# Sensor_AnalogVideo.net
KiCad netlist of a schematic drawn in EAGLE
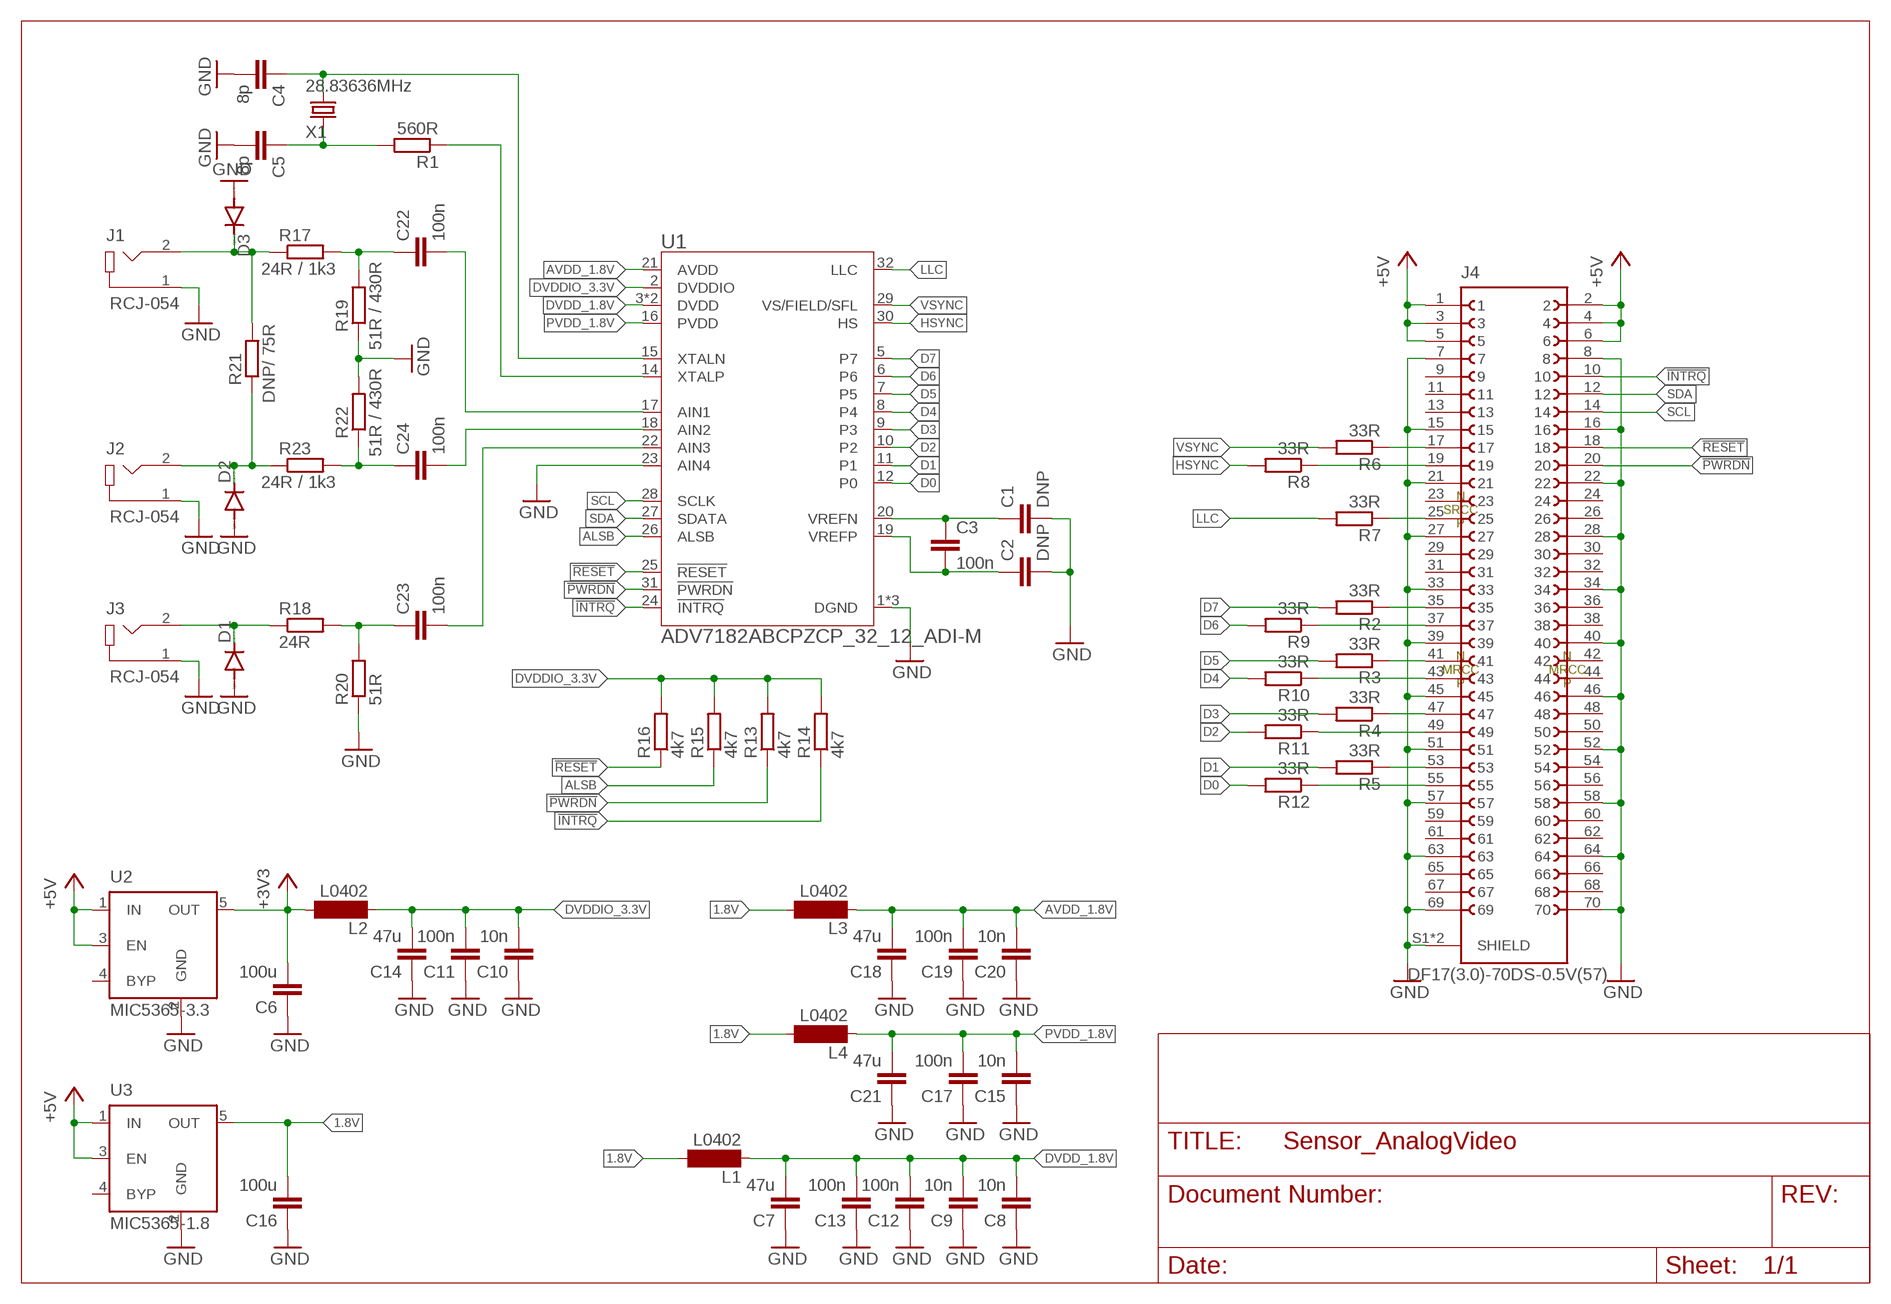
[diagram p0: schematic, sheet 1]

(export (version "E")
  (design (tool "Eeschema 10.0.6"))
  (components
    (comp (ref "C1")
      (value "DNP")
      (footprint "eagle-import:C0402")
      (libsource (lib "eagle-import") (part "rcl_334_C-EUC0402"))
    )
    (comp (ref "C2")
      (value "DNP")
      (footprint "eagle-import:C0402")
      (libsource (lib "eagle-import") (part "rcl_334_C-EUC0402"))
    )
    (comp (ref "C3")
      (value "100n")
      (footprint "eagle-import:C0402")
      (libsource (lib "eagle-import") (part "rcl_334_C-EUC0402"))
    )
    (comp (ref "C4")
      (value "8p")
      (footprint "eagle-import:C0402")
      (libsource (lib "eagle-import") (part "C0402"))
    )
    (comp (ref "C5")
      (value "8p")
      (footprint "eagle-import:C0402")
      (libsource (lib "eagle-import") (part "C0402"))
    )
    (comp (ref "C6")
      (value "100u")
      (footprint "eagle-import:C1206")
      (libsource (lib "eagle-import") (part "rcl_334_C-EUC1206"))
    )
    (comp (ref "C7")
      (value "47u")
      (footprint "eagle-import:C0805")
      (libsource (lib "eagle-import") (part "C-EUC0805"))
    )
    (comp (ref "C8")
      (value "10n")
      (footprint "eagle-import:C0402")
      (libsource (lib "eagle-import") (part "rcl_334_C-EUC0402"))
    )
    (comp (ref "C9")
      (value "10n")
      (footprint "eagle-import:C0402")
      (libsource (lib "eagle-import") (part "rcl_334_C-EUC0402"))
    )
    (comp (ref "C10")
      (value "10n")
      (footprint "eagle-import:C0402")
      (libsource (lib "eagle-import") (part "rcl_334_C-EUC0402"))
    )
    (comp (ref "C11")
      (value "100n")
      (footprint "eagle-import:C0402")
      (libsource (lib "eagle-import") (part "rcl_334_C-EUC0402"))
    )
    (comp (ref "C12")
      (value "100n")
      (footprint "eagle-import:C0402")
      (libsource (lib "eagle-import") (part "rcl_334_C-EUC0402"))
    )
    (comp (ref "C13")
      (value "100n")
      (footprint "eagle-import:C0402")
      (libsource (lib "eagle-import") (part "rcl_334_C-EUC0402"))
    )
    (comp (ref "C14")
      (value "47u")
      (footprint "eagle-import:C0805")
      (libsource (lib "eagle-import") (part "C-EUC0805"))
    )
    (comp (ref "C15")
      (value "10n")
      (footprint "eagle-import:C0402")
      (libsource (lib "eagle-import") (part "rcl_334_C-EUC0402"))
    )
    (comp (ref "C16")
      (value "100u")
      (footprint "eagle-import:C1206")
      (libsource (lib "eagle-import") (part "rcl_334_C-EUC1206"))
    )
    (comp (ref "C17")
      (value "100n")
      (footprint "eagle-import:C0402")
      (libsource (lib "eagle-import") (part "rcl_334_C-EUC0402"))
    )
    (comp (ref "C18")
      (value "47u")
      (footprint "eagle-import:C0805")
      (libsource (lib "eagle-import") (part "C-EUC0805"))
    )
    (comp (ref "C19")
      (value "100n")
      (footprint "eagle-import:C0402")
      (libsource (lib "eagle-import") (part "rcl_334_C-EUC0402"))
    )
    (comp (ref "C20")
      (value "10n")
      (footprint "eagle-import:C0402")
      (libsource (lib "eagle-import") (part "rcl_334_C-EUC0402"))
    )
    (comp (ref "C21")
      (value "47u")
      (footprint "eagle-import:C0805")
      (libsource (lib "eagle-import") (part "C-EUC0805"))
    )
    (comp (ref "C22")
      (value "100n")
      (footprint "eagle-import:C0402")
      (libsource (lib "eagle-import") (part "rcl_334_C-EUC0402"))
    )
    (comp (ref "C23")
      (value "100n")
      (footprint "eagle-import:C0402")
      (libsource (lib "eagle-import") (part "rcl_334_C-EUC0402"))
    )
    (comp (ref "C24")
      (value "100n")
      (footprint "eagle-import:C0402")
      (libsource (lib "eagle-import") (part "rcl_334_C-EUC0402"))
    )
    (comp (ref "D1")
      (value "DIODE-SOD323-W")
      (footprint "eagle-import:SOD323-W")
      (libsource (lib "eagle-import") (part "DIODE-SOD323-W"))
    )
    (comp (ref "D2")
      (value "DIODE-SOD323-W")
      (footprint "eagle-import:SOD323-W")
      (libsource (lib "eagle-import") (part "DIODE-SOD323-W"))
    )
    (comp (ref "D3")
      (value "DIODE-SOD323-W")
      (footprint "eagle-import:SOD323-W")
      (libsource (lib "eagle-import") (part "DIODE-SOD323-W"))
    )
    (comp (ref "J1")
      (value "RCJ-054")
      (footprint "eagle-import:CUI_RCJ-054")
      (fields (field (name "MF") "CUI Devices"))
      (libsource (lib "eagle-import") (part "RCJ-054"))
    )
    (comp (ref "J2")
      (value "RCJ-054")
      (footprint "eagle-import:CUI_RCJ-054")
      (fields (field (name "MF") "CUI Devices"))
      (libsource (lib "eagle-import") (part "RCJ-054"))
    )
    (comp (ref "J3")
      (value "RCJ-054")
      (footprint "eagle-import:CUI_RCJ-054")
      (fields (field (name "MF") "CUI Devices"))
      (libsource (lib "eagle-import") (part "RCJ-054"))
    )
    (comp (ref "J4")
      (value "DF17(3.0)-70DS-0.5V(57)")
      (footprint "eagle-import:DF17(3.0)-70DS-0.5V(57)")
      (libsource (lib "eagle-import") (part "DF17(3.0)-70DS-0.5V(57)"))
    )
    (comp (ref "L1")
      (value "L0402")
      (footprint "eagle-import:C0402")
      (libsource (lib "eagle-import") (part "L0402"))
    )
    (comp (ref "L2")
      (value "L0402")
      (footprint "eagle-import:C0402")
      (libsource (lib "eagle-import") (part "L0402"))
    )
    (comp (ref "L3")
      (value "L0402")
      (footprint "eagle-import:C0402")
      (libsource (lib "eagle-import") (part "L0402"))
    )
    (comp (ref "L4")
      (value "L0402")
      (footprint "eagle-import:C0402")
      (libsource (lib "eagle-import") (part "L0402"))
    )
    (comp (ref "R1")
      (value "560R")
      (footprint "eagle-import:R0402")
      (libsource (lib "eagle-import") (part "R-EU_R0402"))
    )
    (comp (ref "R2")
      (value "33R")
      (footprint "eagle-import:R0402")
      (libsource (lib "eagle-import") (part "R-EU_R0402"))
    )
    (comp (ref "R3")
      (value "33R")
      (footprint "eagle-import:R0402")
      (libsource (lib "eagle-import") (part "R-EU_R0402"))
    )
    (comp (ref "R4")
      (value "33R")
      (footprint "eagle-import:R0402")
      (libsource (lib "eagle-import") (part "R-EU_R0402"))
    )
    (comp (ref "R5")
      (value "33R")
      (footprint "eagle-import:R0402")
      (libsource (lib "eagle-import") (part "R-EU_R0402"))
    )
    (comp (ref "R6")
      (value "33R")
      (footprint "eagle-import:R0402")
      (libsource (lib "eagle-import") (part "R-EU_R0402"))
    )
    (comp (ref "R7")
      (value "33R")
      (footprint "eagle-import:R0402")
      (libsource (lib "eagle-import") (part "R-EU_R0402"))
    )
    (comp (ref "R8")
      (value "33R")
      (footprint "eagle-import:R0402")
      (libsource (lib "eagle-import") (part "R-EU_R0402"))
    )
    (comp (ref "R9")
      (value "33R")
      (footprint "eagle-import:R0402")
      (libsource (lib "eagle-import") (part "R-EU_R0402"))
    )
    (comp (ref "R10")
      (value "33R")
      (footprint "eagle-import:R0402")
      (libsource (lib "eagle-import") (part "R-EU_R0402"))
    )
    (comp (ref "R11")
      (value "33R")
      (footprint "eagle-import:R0402")
      (libsource (lib "eagle-import") (part "R-EU_R0402"))
    )
    (comp (ref "R12")
      (value "33R")
      (footprint "eagle-import:R0402")
      (libsource (lib "eagle-import") (part "R-EU_R0402"))
    )
    (comp (ref "R13")
      (value "4k7")
      (footprint "eagle-import:R0402")
      (libsource (lib "eagle-import") (part "R-EU_R0402"))
    )
    (comp (ref "R14")
      (value "4k7")
      (footprint "eagle-import:R0402")
      (libsource (lib "eagle-import") (part "R-EU_R0402"))
    )
    (comp (ref "R15")
      (value "4k7")
      (footprint "eagle-import:R0402")
      (libsource (lib "eagle-import") (part "R-EU_R0402"))
    )
    (comp (ref "R16")
      (value "4k7")
      (footprint "eagle-import:R0402")
      (libsource (lib "eagle-import") (part "R-EU_R0402"))
    )
    (comp (ref "R17")
      (value "24R / 1k3")
      (footprint "eagle-import:R0603")
      (libsource (lib "eagle-import") (part "R-EU_R0603"))
    )
    (comp (ref "R18")
      (value "24R")
      (footprint "eagle-import:R0603")
      (libsource (lib "eagle-import") (part "R-EU_R0603"))
    )
    (comp (ref "R19")
      (value "51R / 430R")
      (footprint "eagle-import:R0603")
      (libsource (lib "eagle-import") (part "R-EU_R0603"))
    )
    (comp (ref "R20")
      (value "51R")
      (footprint "eagle-import:R0603")
      (libsource (lib "eagle-import") (part "R-EU_R0603"))
    )
    (comp (ref "R21")
      (value "DNP/ 75R")
      (footprint "eagle-import:R0603")
      (libsource (lib "eagle-import") (part "R-EU_R0603"))
    )
    (comp (ref "R22")
      (value "51R / 430R")
      (footprint "eagle-import:R0603")
      (libsource (lib "eagle-import") (part "R-EU_R0603"))
    )
    (comp (ref "R23")
      (value "24R / 1k3")
      (footprint "eagle-import:R0603")
      (libsource (lib "eagle-import") (part "R-EU_R0603"))
    )
    (comp (ref "U1")
      (value "ADV7182ABCPZCP_32_12_ADI-M")
      (footprint "eagle-import:CP_32_12_ADI-M")
      (fields (field (name "MPN") "ADV7182ABCPZ"))
      (libsource (lib "eagle-import") (part "ADV7182ABCPZCP_32_12_ADI-M"))
    )
    (comp (ref "U2")
      (value "MIC5365-3.3")
      (footprint "eagle-import:SOT23-5")
      (libsource (lib "eagle-import") (part "MIC5219XX"))
    )
    (comp (ref "U3")
      (value "MIC5365-1.8")
      (footprint "eagle-import:SOT23-5")
      (libsource (lib "eagle-import") (part "MIC5219XX"))
    )
    (comp (ref "X1")
      (value "28.83636MHz")
      (footprint "eagle-import:2520")
      (libsource (lib "eagle-import") (part "CRYSTAL-2520"))
    )
  )
  (nets
    (net (code "1") (name "+3V3") (class "Default")
      (node (ref "C6") (pin "1") (pinfunction "1_1") (pintype "passive"))
      (node (ref "L2") (pin "2") (pinfunction "2_2") (pintype "passive"))
      (node (ref "U2") (pin "5") (pinfunction "OUT_5") (pintype "output"))
    )
    (net (code "2") (name "+5V") (class "Default")
      (node (ref "J4") (pin "1") (pinfunction "1_1") (pintype "passive"))
      (node (ref "J4") (pin "2") (pinfunction "2_2") (pintype "passive"))
      (node (ref "J4") (pin "3") (pinfunction "3_3") (pintype "passive"))
      (node (ref "J4") (pin "4") (pinfunction "4_4") (pintype "passive"))
      (node (ref "J4") (pin "5") (pinfunction "5_5") (pintype "passive"))
      (node (ref "J4") (pin "6") (pinfunction "6_6") (pintype "passive"))
      (node (ref "U2") (pin "1") (pinfunction "IN_1") (pintype "input"))
      (node (ref "U2") (pin "3") (pinfunction "EN_3") (pintype "input"))
      (node (ref "U3") (pin "1") (pinfunction "IN_1") (pintype "input"))
      (node (ref "U3") (pin "3") (pinfunction "EN_3") (pintype "input"))
    )
    (net (code "3") (name "/~{INTRQ}") (class "Default")
      (node (ref "J4") (pin "10") (pinfunction "10_10") (pintype "passive"))
      (node (ref "R14") (pin "1") (pinfunction "1_1") (pintype "passive"))
      (node (ref "U1") (pin "24") (pinfunction "~{INTRQ}_24") (pintype "passive"))
    )
    (net (code "4") (name "/~{PWRDN}") (class "Default")
      (node (ref "J4") (pin "20") (pinfunction "20_20") (pintype "passive"))
      (node (ref "R13") (pin "1") (pinfunction "1_1") (pintype "passive"))
      (node (ref "U1") (pin "31") (pinfunction "~{PWRDN}_31") (pintype "passive"))
    )
    (net (code "5") (name "/~{RESET}") (class "Default")
      (node (ref "J4") (pin "18") (pinfunction "18_18") (pintype "passive"))
      (node (ref "R16") (pin "1") (pinfunction "1_1") (pintype "passive"))
      (node (ref "U1") (pin "25") (pinfunction "~{RESET}_25") (pintype "passive"))
    )
    (net (code "6") (name "1.8V") (class "Default")
      (node (ref "C16") (pin "1") (pinfunction "1_1") (pintype "passive"))
      (node (ref "L1") (pin "2") (pinfunction "2_2") (pintype "passive"))
      (node (ref "L3") (pin "2") (pinfunction "2_2") (pintype "passive"))
      (node (ref "L4") (pin "2") (pinfunction "2_2") (pintype "passive"))
      (node (ref "U3") (pin "5") (pinfunction "OUT_5") (pintype "output"))
    )
    (net (code "7") (name "ALSB") (class "Default")
      (node (ref "R15") (pin "1") (pinfunction "1_1") (pintype "passive"))
      (node (ref "U1") (pin "26") (pinfunction "ALSB_26") (pintype "passive"))
    )
    (net (code "8") (name "AVDD_1.8V") (class "Default")
      (node (ref "C18") (pin "2") (pinfunction "2_2") (pintype "passive"))
      (node (ref "C19") (pin "2") (pinfunction "2_2") (pintype "passive"))
      (node (ref "C20") (pin "2") (pinfunction "2_2") (pintype "passive"))
      (node (ref "L3") (pin "1") (pinfunction "1_1") (pintype "passive"))
      (node (ref "U1") (pin "21") (pinfunction "AVDD_21") (pintype "passive"))
    )
    (net (code "9") (name "D0") (class "Default")
      (node (ref "R12") (pin "2") (pinfunction "2_2") (pintype "passive"))
      (node (ref "U1") (pin "12") (pinfunction "P0_12") (pintype "passive"))
    )
    (net (code "10") (name "D1") (class "Default")
      (node (ref "R5") (pin "2") (pinfunction "2_2") (pintype "passive"))
      (node (ref "U1") (pin "11") (pinfunction "P1_11") (pintype "passive"))
    )
    (net (code "11") (name "D2") (class "Default")
      (node (ref "R11") (pin "2") (pinfunction "2_2") (pintype "passive"))
      (node (ref "U1") (pin "10") (pinfunction "P2_10") (pintype "passive"))
    )
    (net (code "12") (name "D3") (class "Default")
      (node (ref "R4") (pin "2") (pinfunction "2_2") (pintype "passive"))
      (node (ref "U1") (pin "9") (pinfunction "P3_9") (pintype "passive"))
    )
    (net (code "13") (name "D4") (class "Default")
      (node (ref "R10") (pin "2") (pinfunction "2_2") (pintype "passive"))
      (node (ref "U1") (pin "8") (pinfunction "P4_8") (pintype "passive"))
    )
    (net (code "14") (name "D5") (class "Default")
      (node (ref "R3") (pin "2") (pinfunction "2_2") (pintype "passive"))
      (node (ref "U1") (pin "7") (pinfunction "P5_7") (pintype "passive"))
    )
    (net (code "15") (name "D6") (class "Default")
      (node (ref "R9") (pin "2") (pinfunction "2_2") (pintype "passive"))
      (node (ref "U1") (pin "6") (pinfunction "P6_6") (pintype "passive"))
    )
    (net (code "16") (name "D7") (class "Default")
      (node (ref "R2") (pin "2") (pinfunction "2_2") (pintype "passive"))
      (node (ref "U1") (pin "5") (pinfunction "P7_5") (pintype "passive"))
    )
    (net (code "17") (name "DVDDIO_3.3V") (class "Default")
      (node (ref "C10") (pin "2") (pinfunction "2_2") (pintype "passive"))
      (node (ref "C11") (pin "2") (pinfunction "2_2") (pintype "passive"))
      (node (ref "C14") (pin "2") (pinfunction "2_2") (pintype "passive"))
      (node (ref "L2") (pin "1") (pinfunction "1_1") (pintype "passive"))
      (node (ref "R13") (pin "2") (pinfunction "2_2") (pintype "passive"))
      (node (ref "R14") (pin "2") (pinfunction "2_2") (pintype "passive"))
      (node (ref "R15") (pin "2") (pinfunction "2_2") (pintype "passive"))
      (node (ref "R16") (pin "2") (pinfunction "2_2") (pintype "passive"))
      (node (ref "U1") (pin "2") (pinfunction "DVDDIO_2") (pintype "passive"))
    )
    (net (code "18") (name "DVDD_1.8V") (class "Default")
      (node (ref "C12") (pin "2") (pinfunction "2_2") (pintype "passive"))
      (node (ref "C13") (pin "2") (pinfunction "2_2") (pintype "passive"))
      (node (ref "C7") (pin "2") (pinfunction "2_2") (pintype "passive"))
      (node (ref "C8") (pin "2") (pinfunction "2_2") (pintype "passive"))
      (node (ref "C9") (pin "2") (pinfunction "2_2") (pintype "passive"))
      (node (ref "L1") (pin "1") (pinfunction "1_1") (pintype "passive"))
      (node (ref "U1") (pin "13") (pinfunction "DVDD_13") (pintype "passive"))
      (node (ref "U1") (pin "3") (pinfunction "DVDD_3") (pintype "passive"))
    )
    (net (code "19") (name "GND") (class "Default")
      (node (ref "C1") (pin "2") (pinfunction "2_2") (pintype "passive"))
      (node (ref "C10") (pin "1") (pinfunction "1_1") (pintype "passive"))
      (node (ref "C11") (pin "1") (pinfunction "1_1") (pintype "passive"))
      (node (ref "C12") (pin "1") (pinfunction "1_1") (pintype "passive"))
      (node (ref "C13") (pin "1") (pinfunction "1_1") (pintype "passive"))
      (node (ref "C14") (pin "1") (pinfunction "1_1") (pintype "passive"))
      (node (ref "C15") (pin "1") (pinfunction "1_1") (pintype "passive"))
      (node (ref "C16") (pin "2") (pinfunction "2_2") (pintype "passive"))
      (node (ref "C17") (pin "1") (pinfunction "1_1") (pintype "passive"))
      (node (ref "C18") (pin "1") (pinfunction "1_1") (pintype "passive"))
      (node (ref "C19") (pin "1") (pinfunction "1_1") (pintype "passive"))
      (node (ref "C2") (pin "2") (pinfunction "2_2") (pintype "passive"))
      (node (ref "C20") (pin "1") (pinfunction "1_1") (pintype "passive"))
      (node (ref "C21") (pin "1") (pinfunction "1_1") (pintype "passive"))
      (node (ref "C4") (pin "2") (pinfunction "2_2") (pintype "passive"))
      (node (ref "C5") (pin "2") (pinfunction "2_2") (pintype "passive"))
      (node (ref "C6") (pin "2") (pinfunction "2_2") (pintype "passive"))
      (node (ref "C7") (pin "1") (pinfunction "1_1") (pintype "passive"))
      (node (ref "C8") (pin "1") (pinfunction "1_1") (pintype "passive"))
      (node (ref "C9") (pin "1") (pinfunction "1_1") (pintype "passive"))
      (node (ref "D1") (pin "A") (pinfunction "A_A") (pintype "passive"))
      (node (ref "D2") (pin "A") (pinfunction "A_A") (pintype "passive"))
      (node (ref "D3") (pin "A") (pinfunction "A_A") (pintype "passive"))
      (node (ref "J1") (pin "1") (pinfunction "1_1") (pintype "passive"))
      (node (ref "J2") (pin "1") (pinfunction "1_1") (pintype "passive"))
      (node (ref "J3") (pin "1") (pinfunction "1_1") (pintype "passive"))
      (node (ref "J4") (pin "15") (pinfunction "15_15") (pintype "passive"))
      (node (ref "J4") (pin "16") (pinfunction "16_16") (pintype "passive"))
      (node (ref "J4") (pin "21") (pinfunction "21_21") (pintype "passive"))
      (node (ref "J4") (pin "22") (pinfunction "22_22") (pintype "passive"))
      (node (ref "J4") (pin "27") (pinfunction "27_27") (pintype "passive"))
      (node (ref "J4") (pin "28") (pinfunction "28_28") (pintype "passive"))
      (node (ref "J4") (pin "33") (pinfunction "33_33") (pintype "passive"))
      (node (ref "J4") (pin "34") (pinfunction "34_34") (pintype "passive"))
      (node (ref "J4") (pin "39") (pinfunction "39_39") (pintype "passive"))
      (node (ref "J4") (pin "40") (pinfunction "40_40") (pintype "passive"))
      (node (ref "J4") (pin "45") (pinfunction "45_45") (pintype "passive"))
      (node (ref "J4") (pin "46") (pinfunction "46_46") (pintype "passive"))
      (node (ref "J4") (pin "51") (pinfunction "51_51") (pintype "passive"))
      (node (ref "J4") (pin "52") (pinfunction "52_52") (pintype "passive"))
      (node (ref "J4") (pin "57") (pinfunction "57_57") (pintype "passive"))
      (node (ref "J4") (pin "58") (pinfunction "58_58") (pintype "passive"))
      (node (ref "J4") (pin "63") (pinfunction "63_63") (pintype "passive"))
      (node (ref "J4") (pin "64") (pinfunction "64_64") (pintype "passive"))
      (node (ref "J4") (pin "69") (pinfunction "69_69") (pintype "passive"))
      (node (ref "J4") (pin "7") (pinfunction "7_7") (pintype "passive"))
      (node (ref "J4") (pin "70") (pinfunction "70_70") (pintype "passive"))
      (node (ref "J4") (pin "8") (pinfunction "8_8") (pintype "passive"))
      (node (ref "J4") (pin "S1") (pinfunction "SHIELD_S1") (pintype "passive"))
      (node (ref "J4") (pin "S2") (pinfunction "SHIELD_S2") (pintype "passive"))
      (node (ref "R19") (pin "1") (pinfunction "1_1") (pintype "passive"))
      (node (ref "R20") (pin "1") (pinfunction "1_1") (pintype "passive"))
      (node (ref "R22") (pin "2") (pinfunction "2_2") (pintype "passive"))
      (node (ref "U1") (pin "1") (pinfunction "DGND_1") (pintype "passive"))
      (node (ref "U1") (pin "23") (pinfunction "AIN4_23") (pintype "passive"))
      (node (ref "U1") (pin "33") (pinfunction "DGND_33") (pintype "passive"))
      (node (ref "U1") (pin "4") (pinfunction "DGND_4") (pintype "passive"))
      (node (ref "U2") (pin "2") (pinfunction "GND_2") (pintype "power_in"))
      (node (ref "U3") (pin "2") (pinfunction "GND_2") (pintype "power_in"))
    )
    (net (code "20") (name "HSYNC") (class "Default")
      (node (ref "R8") (pin "2") (pinfunction "2_2") (pintype "passive"))
      (node (ref "U1") (pin "30") (pinfunction "HS_30") (pintype "passive"))
    )
    (net (code "21") (name "LLC") (class "Default")
      (node (ref "R7") (pin "2") (pinfunction "2_2") (pintype "passive"))
      (node (ref "U1") (pin "32") (pinfunction "LLC_32") (pintype "passive"))
    )
    (net (code "22") (name "Net-(C22-Pad1)") (class "Default")
      (node (ref "C22") (pin "1") (pinfunction "1_1") (pintype "passive"))
      (node (ref "R17") (pin "2") (pinfunction "2_2") (pintype "passive"))
      (node (ref "R19") (pin "2") (pinfunction "2_2") (pintype "passive"))
    )
    (net (code "23") (name "Net-(C23-Pad1)") (class "Default")
      (node (ref "C23") (pin "1") (pinfunction "1_1") (pintype "passive"))
      (node (ref "R18") (pin "2") (pinfunction "2_2") (pintype "passive"))
      (node (ref "R20") (pin "2") (pinfunction "2_2") (pintype "passive"))
    )
    (net (code "24") (name "Net-(C24-Pad1)") (class "Default")
      (node (ref "C24") (pin "1") (pinfunction "1_1") (pintype "passive"))
      (node (ref "R22") (pin "1") (pinfunction "1_1") (pintype "passive"))
      (node (ref "R23") (pin "2") (pinfunction "2_2") (pintype "passive"))
    )
    (net (code "25") (name "Net-(D1-PadC)") (class "Default")
      (node (ref "D1") (pin "C") (pinfunction "C_C") (pintype "passive"))
      (node (ref "J3") (pin "2") (pinfunction "2_2") (pintype "passive"))
      (node (ref "R18") (pin "1") (pinfunction "1_1") (pintype "passive"))
    )
    (net (code "26") (name "Net-(D2-PadC)") (class "Default")
      (node (ref "D2") (pin "C") (pinfunction "C_C") (pintype "passive"))
      (node (ref "J2") (pin "2") (pinfunction "2_2") (pintype "passive"))
      (node (ref "R21") (pin "1") (pinfunction "1_1") (pintype "passive"))
      (node (ref "R23") (pin "1") (pinfunction "1_1") (pintype "passive"))
    )
    (net (code "27") (name "Net-(D3-PadC)") (class "Default")
      (node (ref "D3") (pin "C") (pinfunction "C_C") (pintype "passive"))
      (node (ref "J1") (pin "2") (pinfunction "2_2") (pintype "passive"))
      (node (ref "R17") (pin "1") (pinfunction "1_1") (pintype "passive"))
      (node (ref "R21") (pin "2") (pinfunction "2_2") (pintype "passive"))
    )
    (net (code "28") (name "Net-(J4-Pad17)") (class "Default")
      (node (ref "J4") (pin "17") (pinfunction "17_17") (pintype "passive"))
      (node (ref "R6") (pin "1") (pinfunction "1_1") (pintype "passive"))
    )
    (net (code "29") (name "Net-(J4-Pad19)") (class "Default")
      (node (ref "J4") (pin "19") (pinfunction "19_19") (pintype "passive"))
      (node (ref "R8") (pin "1") (pinfunction "1_1") (pintype "passive"))
    )
    (net (code "30") (name "Net-(J4-Pad25)") (class "Default")
      (node (ref "J4") (pin "25") (pinfunction "25_25") (pintype "passive"))
      (node (ref "R7") (pin "1") (pinfunction "1_1") (pintype "passive"))
    )
    (net (code "31") (name "Net-(J4-Pad35)") (class "Default")
      (node (ref "J4") (pin "35") (pinfunction "35_35") (pintype "passive"))
      (node (ref "R2") (pin "1") (pinfunction "1_1") (pintype "passive"))
    )
    (net (code "32") (name "Net-(J4-Pad37)") (class "Default")
      (node (ref "J4") (pin "37") (pinfunction "37_37") (pintype "passive"))
      (node (ref "R9") (pin "1") (pinfunction "1_1") (pintype "passive"))
    )
    (net (code "33") (name "Net-(J4-Pad41)") (class "Default")
      (node (ref "J4") (pin "41") (pinfunction "41_41") (pintype "passive"))
      (node (ref "R3") (pin "1") (pinfunction "1_1") (pintype "passive"))
    )
    (net (code "34") (name "Net-(J4-Pad43)") (class "Default")
      (node (ref "J4") (pin "43") (pinfunction "43_43") (pintype "passive"))
      (node (ref "R10") (pin "1") (pinfunction "1_1") (pintype "passive"))
    )
    (net (code "35") (name "Net-(J4-Pad47)") (class "Default")
      (node (ref "J4") (pin "47") (pinfunction "47_47") (pintype "passive"))
      (node (ref "R4") (pin "1") (pinfunction "1_1") (pintype "passive"))
    )
    (net (code "36") (name "Net-(J4-Pad49)") (class "Default")
      (node (ref "J4") (pin "49") (pinfunction "49_49") (pintype "passive"))
      (node (ref "R11") (pin "1") (pinfunction "1_1") (pintype "passive"))
    )
    (net (code "37") (name "Net-(J4-Pad53)") (class "Default")
      (node (ref "J4") (pin "53") (pinfunction "53_53") (pintype "passive"))
      (node (ref "R5") (pin "1") (pinfunction "1_1") (pintype "passive"))
    )
    (net (code "38") (name "Net-(J4-Pad55)") (class "Default")
      (node (ref "J4") (pin "55") (pinfunction "55_55") (pintype "passive"))
      (node (ref "R12") (pin "1") (pinfunction "1_1") (pintype "passive"))
    )
    (net (code "39") (name "Net-(U1-AIN1)") (class "Default")
      (node (ref "C22") (pin "2") (pinfunction "2_2") (pintype "passive"))
      (node (ref "U1") (pin "17") (pinfunction "AIN1_17") (pintype "passive"))
    )
    (net (code "40") (name "Net-(U1-AIN2)") (class "Default")
      (node (ref "C24") (pin "2") (pinfunction "2_2") (pintype "passive"))
      (node (ref "U1") (pin "18") (pinfunction "AIN2_18") (pintype "passive"))
    )
    (net (code "41") (name "Net-(U1-AIN3)") (class "Default")
      (node (ref "C23") (pin "2") (pinfunction "2_2") (pintype "passive"))
      (node (ref "U1") (pin "22") (pinfunction "AIN3_22") (pintype "passive"))
    )
    (net (code "42") (name "Net-(U1-VREFN)") (class "Default")
      (node (ref "C1") (pin "1") (pinfunction "1_1") (pintype "passive"))
      (node (ref "C3") (pin "1") (pinfunction "1_1") (pintype "passive"))
      (node (ref "U1") (pin "20") (pinfunction "VREFN_20") (pintype "passive"))
    )
    (net (code "43") (name "Net-(U1-VREFP)") (class "Default")
      (node (ref "C2") (pin "1") (pinfunction "1_1") (pintype "passive"))
      (node (ref "C3") (pin "2") (pinfunction "2_2") (pintype "passive"))
      (node (ref "U1") (pin "19") (pinfunction "VREFP_19") (pintype "passive"))
    )
    (net (code "44") (name "Net-(U1-XTALN)") (class "Default")
      (node (ref "C4") (pin "1") (pinfunction "1_1") (pintype "passive"))
      (node (ref "U1") (pin "15") (pinfunction "XTALN_15") (pintype "passive"))
      (node (ref "X1") (pin "1") (pinfunction "1_1") (pintype "passive"))
    )
    (net (code "45") (name "Net-(U1-XTALP)") (class "Default")
      (node (ref "R1") (pin "1") (pinfunction "1_1") (pintype "passive"))
      (node (ref "U1") (pin "14") (pinfunction "XTALP_14") (pintype "passive"))
    )
    (net (code "46") (name "Net-(X1-2)") (class "Default")
      (node (ref "C5") (pin "1") (pinfunction "1_1") (pintype "passive"))
      (node (ref "R1") (pin "2") (pinfunction "2_2") (pintype "passive"))
      (node (ref "X1") (pin "3") (pinfunction "2_3") (pintype "passive"))
    )
    (net (code "47") (name "PVDD_1.8V") (class "Default")
      (node (ref "C15") (pin "2") (pinfunction "2_2") (pintype "passive"))
      (node (ref "C17") (pin "2") (pinfunction "2_2") (pintype "passive"))
      (node (ref "C21") (pin "2") (pinfunction "2_2") (pintype "passive"))
      (node (ref "L4") (pin "1") (pinfunction "1_1") (pintype "passive"))
      (node (ref "U1") (pin "16") (pinfunction "PVDD_16") (pintype "passive"))
    )
    (net (code "48") (name "SCL") (class "Default")
      (node (ref "J4") (pin "14") (pinfunction "14_14") (pintype "passive"))
      (node (ref "U1") (pin "28") (pinfunction "SCLK_28") (pintype "passive"))
    )
    (net (code "49") (name "SDA") (class "Default")
      (node (ref "J4") (pin "12") (pinfunction "12_12") (pintype "passive"))
      (node (ref "U1") (pin "27") (pinfunction "SDATA_27") (pintype "passive"))
    )
    (net (code "50") (name "VSYNC") (class "Default")
      (node (ref "R6") (pin "2") (pinfunction "2_2") (pintype "passive"))
      (node (ref "U1") (pin "29") (pinfunction "VS/FIELD/SFL_29") (pintype "passive"))
    )
    (net (code "51") (name "unconnected-(J4-Pad9)") (class "Default")
      (node (ref "J4") (pin "9") (pinfunction "9_9") (pintype "passive"))
    )
    (net (code "52") (name "unconnected-(J4-Pad11)") (class "Default")
      (node (ref "J4") (pin "11") (pinfunction "11_11") (pintype "passive"))
    )
    (net (code "53") (name "unconnected-(J4-Pad13)") (class "Default")
      (node (ref "J4") (pin "13") (pinfunction "13_13") (pintype "passive"))
    )
    (net (code "54") (name "unconnected-(J4-Pad23)") (class "Default")
      (node (ref "J4") (pin "23") (pinfunction "23_23") (pintype "passive"))
    )
    (net (code "55") (name "unconnected-(J4-Pad24)") (class "Default")
      (node (ref "J4") (pin "24") (pinfunction "24_24") (pintype "passive"))
    )
    (net (code "56") (name "unconnected-(J4-Pad26)") (class "Default")
      (node (ref "J4") (pin "26") (pinfunction "26_26") (pintype "passive"))
    )
    (net (code "57") (name "unconnected-(J4-Pad29)") (class "Default")
      (node (ref "J4") (pin "29") (pinfunction "29_29") (pintype "passive"))
    )
    (net (code "58") (name "unconnected-(J4-Pad30)") (class "Default")
      (node (ref "J4") (pin "30") (pinfunction "30_30") (pintype "passive"))
    )
    (net (code "59") (name "unconnected-(J4-Pad31)") (class "Default")
      (node (ref "J4") (pin "31") (pinfunction "31_31") (pintype "passive"))
    )
    (net (code "60") (name "unconnected-(J4-Pad32)") (class "Default")
      (node (ref "J4") (pin "32") (pinfunction "32_32") (pintype "passive"))
    )
    (net (code "61") (name "unconnected-(J4-Pad36)") (class "Default")
      (node (ref "J4") (pin "36") (pinfunction "36_36") (pintype "passive"))
    )
    (net (code "62") (name "unconnected-(J4-Pad38)") (class "Default")
      (node (ref "J4") (pin "38") (pinfunction "38_38") (pintype "passive"))
    )
    (net (code "63") (name "unconnected-(J4-Pad42)") (class "Default")
      (node (ref "J4") (pin "42") (pinfunction "42_42") (pintype "passive"))
    )
    (net (code "64") (name "unconnected-(J4-Pad44)") (class "Default")
      (node (ref "J4") (pin "44") (pinfunction "44_44") (pintype "passive"))
    )
    (net (code "65") (name "unconnected-(J4-Pad48)") (class "Default")
      (node (ref "J4") (pin "48") (pinfunction "48_48") (pintype "passive"))
    )
    (net (code "66") (name "unconnected-(J4-Pad50)") (class "Default")
      (node (ref "J4") (pin "50") (pinfunction "50_50") (pintype "passive"))
    )
    (net (code "67") (name "unconnected-(J4-Pad54)") (class "Default")
      (node (ref "J4") (pin "54") (pinfunction "54_54") (pintype "passive"))
    )
    (net (code "68") (name "unconnected-(J4-Pad56)") (class "Default")
      (node (ref "J4") (pin "56") (pinfunction "56_56") (pintype "passive"))
    )
    (net (code "69") (name "unconnected-(J4-Pad59)") (class "Default")
      (node (ref "J4") (pin "59") (pinfunction "59_59") (pintype "passive"))
    )
    (net (code "70") (name "unconnected-(J4-Pad60)") (class "Default")
      (node (ref "J4") (pin "60") (pinfunction "60_60") (pintype "passive"))
    )
    (net (code "71") (name "unconnected-(J4-Pad61)") (class "Default")
      (node (ref "J4") (pin "61") (pinfunction "61_61") (pintype "passive"))
    )
    (net (code "72") (name "unconnected-(J4-Pad62)") (class "Default")
      (node (ref "J4") (pin "62") (pinfunction "62_62") (pintype "passive"))
    )
    (net (code "73") (name "unconnected-(J4-Pad65)") (class "Default")
      (node (ref "J4") (pin "65") (pinfunction "65_65") (pintype "passive"))
    )
    (net (code "74") (name "unconnected-(J4-Pad66)") (class "Default")
      (node (ref "J4") (pin "66") (pinfunction "66_66") (pintype "passive"))
    )
    (net (code "75") (name "unconnected-(J4-Pad67)") (class "Default")
      (node (ref "J4") (pin "67") (pinfunction "67_67") (pintype "passive"))
    )
    (net (code "76") (name "unconnected-(J4-Pad68)") (class "Default")
      (node (ref "J4") (pin "68") (pinfunction "68_68") (pintype "passive"))
    )
    (net (code "77") (name "unconnected-(U2-BYP-Pad4)") (class "Default")
      (node (ref "U2") (pin "4") (pinfunction "BYP_4") (pintype "passive"))
    )
    (net (code "78") (name "unconnected-(U3-BYP-Pad4)") (class "Default")
      (node (ref "U3") (pin "4") (pinfunction "BYP_4") (pintype "passive"))
    )
  )
)
